# lipo_alarm.net
KiCad netlist of a schematic drawn in Altium Designer
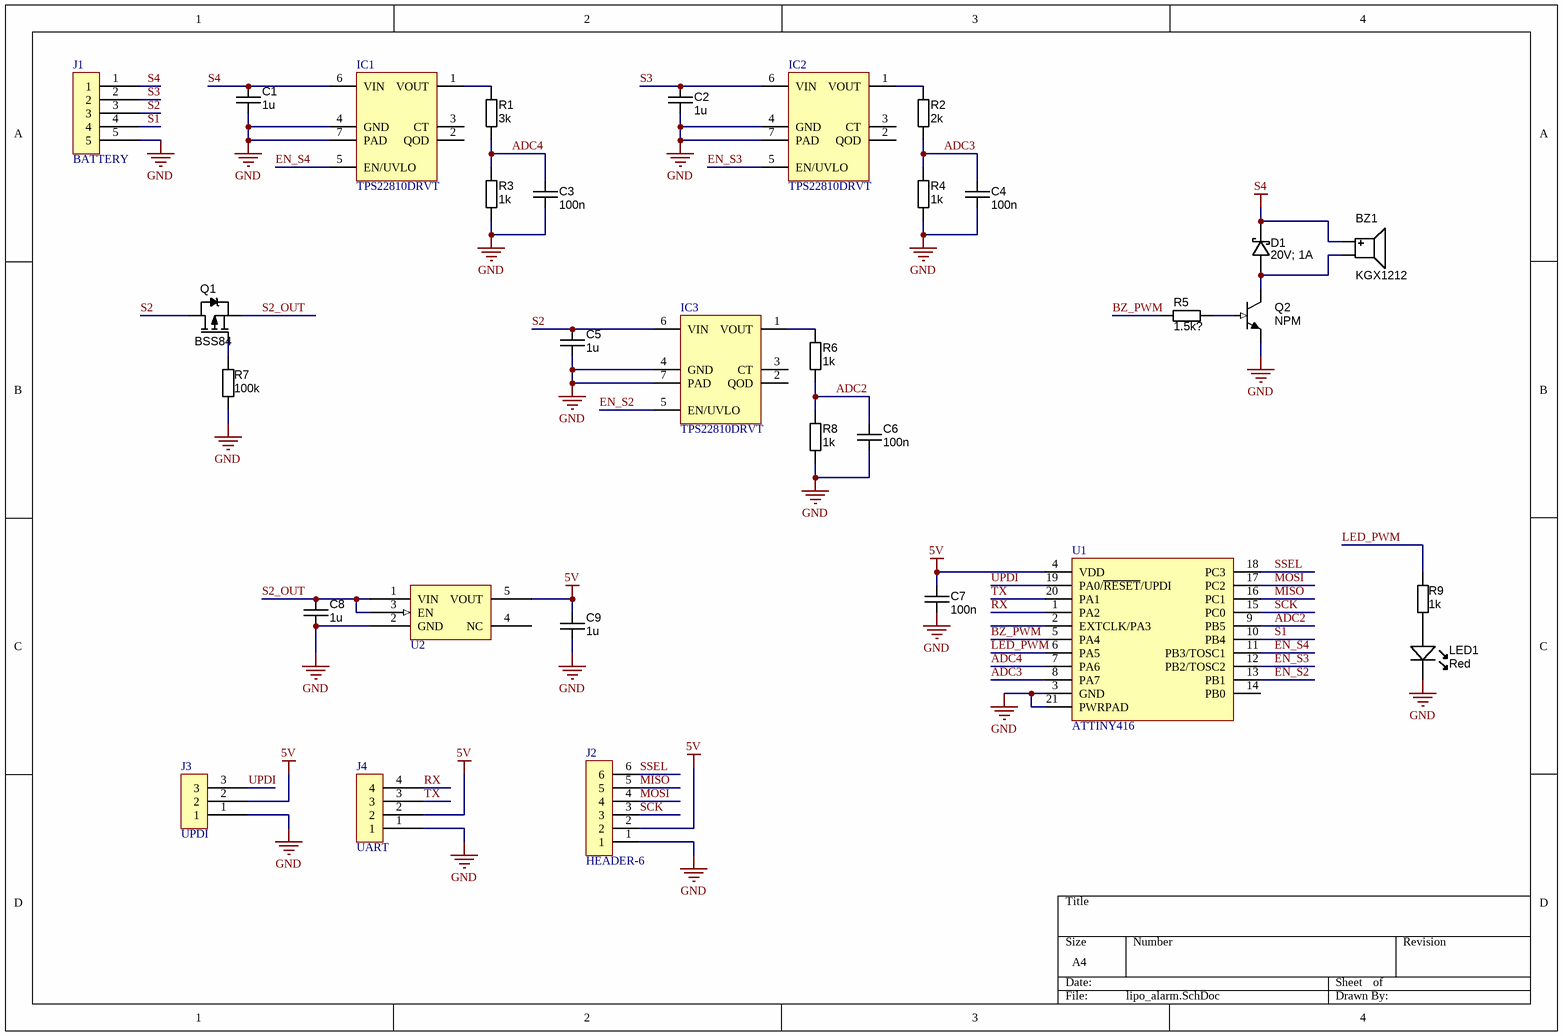
[diagram p0: lipo_alarm.SchDoc]

(export (version "E")
  (design (tool "Eeschema 10.0.6"))
  (components
    (comp (ref "BZ1") (value "KGX1212") (footprint "KXG1212") (libsource (lib "misc") (part "BUZZER")))
    (comp (ref "C1")
      (value "1u")
      (footprint "CAPC1608X90N")
      (description "Capacitor SMD Cer 1uF 10% 16V X7R 0603")
      (fields (field (name "TOLERANCE") "±10%"))
      (libsource (lib "PBL - Capacitors") (part "CAPC_1u_0603_X7R_16V_10%"))
    )
    (comp (ref "C2")
      (value "1u")
      (footprint "CAPC1608X90N")
      (description "Capacitor SMD Cer 1uF 10% 50V X7R 0603")
      (fields (field (name "TOLERANCE") "±10%"))
      (libsource (lib "PBL - Capacitors") (part "CAPC_100n_0603_X7R_50V_10%"))
    )
    (comp (ref "C3")
      (value "100n")
      (footprint "CAPC1608X90N")
      (description "Capacitor SMD Cer 100nF 10% 50V X7R 0603")
      (fields (field (name "TOLERANCE") "±10%"))
      (libsource (lib "PBL - Capacitors") (part "CAPC_100n_0603_X7R_50V_10%"))
    )
    (comp (ref "C4")
      (value "100n")
      (footprint "CAPC1608X90N")
      (description "Capacitor SMD Cer 100nF 10% 50V X7R 0603")
      (fields (field (name "TOLERANCE") "±10%"))
      (libsource (lib "PBL - Capacitors") (part "CAPC_100n_0603_X7R_50V_10%"))
    )
    (comp (ref "C5")
      (value "1u")
      (footprint "CAPC1608X90N")
      (description "Capacitor SMD Cer 1uF 10% 16V X7R 0603")
      (fields (field (name "TOLERANCE") "±10%"))
      (libsource (lib "PBL - Capacitors") (part "CAPC_1u_0603_X7R_16V_10%"))
    )
    (comp (ref "C6")
      (value "100n")
      (footprint "CAPC1608X90N")
      (description "Capacitor SMD Cer 100nF 10% 50V X7R 0603")
      (fields (field (name "TOLERANCE") "±10%"))
      (libsource (lib "PBL - Capacitors") (part "CAPC_100n_0603_X7R_50V_10%"))
    )
    (comp (ref "C7")
      (value "100n")
      (footprint "CAPC1608X90N")
      (description "Capacitor SMD Cer 100nF 10% 50V X7R 0603")
      (fields (field (name "TOLERANCE") "±10%"))
      (libsource (lib "PBL - Capacitors") (part "CAPC_100n_0603_X7R_50V_10%"))
    )
    (comp (ref "C8")
      (value "1u")
      (footprint "CAPC1608X90N")
      (description "Capacitor SMD Cer 2.2uF 10% 10V X5R 0603")
      (fields (field (name "TOLERANCE") "±10%"))
      (libsource (lib "PBL - Capacitors") (part "CAPC_2u2_0603_10V_10%"))
    )
    (comp (ref "C9")
      (value "1u")
      (footprint "CAPC1608X90N")
      (description "Capacitor SMD Cer 2.2uF 10% 10V X5R 0603")
      (fields (field (name "TOLERANCE") "±10%"))
      (libsource (lib "PBL - Capacitors") (part "CAPC_2u2_0603_10V_10%"))
    )
    (comp (ref "D1")
      (value "20V; 1A")
      (footprint "SOD123")
      (description "Diode Schottky SMD 20V 1A SOD123")
      (libsource (lib "PBL - Diodes") (part "DIODE_SCHOTTKY_40V_1A"))
    )
    (comp (ref "IC1")
      (value "TPS22810DRVT")
      (footprint "WSON-6")
      (description "Power Load Switch, 18Vin, 3A, 0.079R, WSON-6, High Side,  TPS22810, TEXAS INSTRUMENTS")
      (fields (field (name "MANUFACTURER") "Texas Instruments"))
      (libsource (lib "power") (part "TPS22810DRVT"))
    )
    (comp (ref "IC2")
      (value "TPS22810DRVT")
      (footprint "WSON-6")
      (description "Power Load Switch, 18Vin, 3A, 0.079R, WSON-6, High Side,  TPS22810, TEXAS INSTRUMENTS")
      (fields (field (name "MANUFACTURER") "Texas Instruments"))
      (libsource (lib "power") (part "TPS22810DRVT"))
    )
    (comp (ref "IC3")
      (value "TPS22810DRVT")
      (footprint "WSON-6")
      (description "Power Load Switch, 18Vin, 3A, 0.079R, WSON-6, High Side,  TPS22810, TEXAS INSTRUMENTS")
      (fields (field (name "MANUFACTURER") "Texas Instruments"))
      (libsource (lib "power") (part "TPS22810DRVT"))
    )
    (comp (ref "J1")
      (value "BATTERY")
      (footprint "JST-XH-5-TH-PCB-CUTOUT")
      (libsource (lib "connectors") (part "HEADER-5"))
    )
    (comp (ref "J2")
      (value "HEADER-6")
      (footprint "MICRO-MATCH-FOB-06")
      (libsource (lib "connectors_micromatch") (part "HEADER-6"))
    )
    (comp (ref "J3")
      (value "UPDI")
      (footprint "PADS-3-1020")
      (libsource (lib "connectors") (part "HEADER-3"))
    )
    (comp (ref "J4")
      (value "UART")
      (footprint "PADS-4-1020")
      (libsource (lib "connectors") (part "HEADER-4"))
    )
    (comp (ref "LED1")
      (value "Red")
      (footprint "LED-0805S-SIDELED-2.1X0.6X1.0")
      (description "LED SMD SIDELED Red 630nm 250mcd 0805")
      (fields (field (name "COLOR") "Red"))
      (libsource (lib "PBL - Light Sources") (part "LED_SMD_RED_0805RA_250mcd"))
    )
    (comp (ref "Q1")
      (value "BSS84")
      (footprint "SOT23-3")
      (description "MOSFET SMD P-CH 50V 130mA SOT23-3")
      (libsource (lib "PBL - Transistors") (part "MOSFET_BSS84"))
    )
    (comp (ref "Q2")
      (value "NPM")
      (footprint "SOT23-3")
      (description "Transistor SMD NPN 15V 3A SOT-23")
      (libsource (lib "PBL - Transistors") (part "NPN_FMMT617TA"))
    )
    (comp (ref "R1")
      (value "3k")
      (footprint "RESC1608X55N")
      (description "Resistor SMD chip 1k Ohm 0.1W 5% 0603")
      (fields (field (name "TOLERANCE") "±5%"))
      (libsource (lib "PBL - Resistors") (part "RES_1K_0603_5%"))
    )
    (comp (ref "R2")
      (value "2k")
      (footprint "RESC1608X55N")
      (description "Resistor SMD chip 1k Ohm 0.1W 5% 0603")
      (fields (field (name "TOLERANCE") "±5%"))
      (libsource (lib "PBL - Resistors") (part "RES_1K_0603_5%"))
    )
    (comp (ref "R3")
      (value "1k")
      (footprint "RESC1608X55N")
      (description "Resistor SMD chip 1k Ohm 0.1W 5% 0603")
      (fields (field (name "TOLERANCE") "±5%"))
      (libsource (lib "PBL - Resistors") (part "RES_1K_0603_5%"))
    )
    (comp (ref "R4")
      (value "1k")
      (footprint "RESC1608X55N")
      (description "Resistor SMD chip 1k Ohm 0.1W 5% 0603")
      (fields (field (name "TOLERANCE") "±5%"))
      (libsource (lib "PBL - Resistors") (part "RES_1K_0603_5%"))
    )
    (comp (ref "R5")
      (value "1.5k?")
      (footprint "RESC1608X55N")
      (description "Resistor SMD chip 1k Ohm 0.1W 5% 0603")
      (fields (field (name "TOLERANCE") "±5%"))
      (libsource (lib "") (part "RES_1K_0603_5%_1"))
    )
    (comp (ref "R6")
      (value "1k")
      (footprint "RESC1608X55N")
      (description "Resistor SMD chip 1k Ohm 0.1W 5% 0603")
      (fields (field (name "TOLERANCE") "±5%"))
      (libsource (lib "PBL - Resistors") (part "RES_1K_0603_5%"))
    )
    (comp (ref "R7")
      (value "100k")
      (footprint "RESC1608X55N")
      (description "Resistor SMD chip 1k Ohm 0.1W 5% 0603")
      (fields (field (name "TOLERANCE") "±5%"))
      (libsource (lib "") (part "RES_1K_0603_5%_1"))
    )
    (comp (ref "R8")
      (value "1k")
      (footprint "RESC1608X55N")
      (description "Resistor SMD chip 1k Ohm 0.1W 5% 0603")
      (fields (field (name "TOLERANCE") "±5%"))
      (libsource (lib "PBL - Resistors") (part "RES_1K_0603_5%"))
    )
    (comp (ref "R9")
      (value "1k")
      (footprint "RESC1608X55N")
      (description "Resistor SMD chip 1k Ohm 0.1W 5% 0603")
      (fields (field (name "TOLERANCE") "±5%"))
      (libsource (lib "PBL - Resistors") (part "RES_1K_0603_5%"))
    )
    (comp (ref "U1")
      (value "ATTINY416")
      (footprint "QFN40P300X300X90_HS-21M")
      (libsource (lib "atmel") (part "ATTINY416"))
    )
    (comp (ref "U2")
      (value "LDO-SOT23-5")
      (footprint "SOT23-5")
      (libsource (lib "power") (part "LDO-SOT23-5"))
    )
  )
  (nets
    (net (code "1") (name "/ADC2") (class "Default")
      (node (ref "C6") (pin "1") (pintype "passive"))
      (node (ref "R6") (pin "2") (pinfunction "2_2") (pintype "passive"))
      (node (ref "R8") (pin "1") (pinfunction "1_1") (pintype "passive"))
      (node (ref "U1") (pin "9") (pinfunction "PB5_9") (pintype "passive"))
    )
    (net (code "2") (name "/ADC3") (class "Default")
      (node (ref "C4") (pin "1") (pintype "passive"))
      (node (ref "R2") (pin "2") (pinfunction "2_2") (pintype "passive"))
      (node (ref "R4") (pin "1") (pinfunction "1_1") (pintype "passive"))
      (node (ref "U1") (pin "8") (pinfunction "PA7_8") (pintype "passive"))
    )
    (net (code "3") (name "/ADC4") (class "Default")
      (node (ref "C3") (pin "1") (pintype "passive"))
      (node (ref "R1") (pin "2") (pinfunction "2_2") (pintype "passive"))
      (node (ref "R3") (pin "1") (pinfunction "1_1") (pintype "passive"))
      (node (ref "U1") (pin "7") (pinfunction "PA6_7") (pintype "passive"))
    )
    (net (code "4") (name "/BZ_PWM") (class "Default")
      (node (ref "R5") (pin "1") (pinfunction "1_1") (pintype "passive"))
      (node (ref "U1") (pin "5") (pinfunction "PA4_5") (pintype "passive"))
    )
    (net (code "5") (name "/EN_S2") (class "Default")
      (node (ref "IC3") (pin "5") (pinfunction "EN/UVLO_5") (pintype "passive"))
      (node (ref "U1") (pin "13") (pinfunction "PB1_13") (pintype "passive"))
    )
    (net (code "6") (name "/EN_S3") (class "Default")
      (node (ref "IC2") (pin "5") (pinfunction "EN/UVLO_5") (pintype "passive"))
      (node (ref "U1") (pin "12") (pinfunction "PB2/TOSC2_12") (pintype "passive"))
    )
    (net (code "7") (name "/EN_S4") (class "Default")
      (node (ref "IC1") (pin "5") (pinfunction "EN/UVLO_5") (pintype "passive"))
      (node (ref "U1") (pin "11") (pinfunction "PB3/TOSC1_11") (pintype "passive"))
    )
    (net (code "8") (name "/LED_PWM") (class "Default")
      (node (ref "R9") (pin "1") (pinfunction "1_1") (pintype "passive"))
      (node (ref "U1") (pin "6") (pinfunction "PA5_6") (pintype "passive"))
    )
    (net (code "9") (name "/MISO") (class "Default")
      (node (ref "J2") (pin "5") (pinfunction "5_5") (pintype "passive"))
      (node (ref "U1") (pin "16") (pinfunction "PC1_16") (pintype "passive"))
    )
    (net (code "10") (name "/MOSI") (class "Default")
      (node (ref "J2") (pin "4") (pinfunction "4_4") (pintype "passive"))
      (node (ref "U1") (pin "17") (pinfunction "PC2_17") (pintype "passive"))
    )
    (net (code "11") (name "/RX") (class "Default")
      (node (ref "J4") (pin "4") (pinfunction "4_4") (pintype "passive"))
      (node (ref "U1") (pin "1") (pinfunction "PA2_1") (pintype "passive"))
    )
    (net (code "12") (name "/S1") (class "Default")
      (node (ref "J1") (pin "4") (pinfunction "4_4") (pintype "passive"))
      (node (ref "U1") (pin "10") (pinfunction "PB4_10") (pintype "passive"))
    )
    (net (code "13") (name "/S2") (class "Default")
      (node (ref "C5") (pin "1") (pintype "passive"))
      (node (ref "IC3") (pin "6") (pinfunction "VIN_6") (pintype "passive"))
      (node (ref "J1") (pin "3") (pinfunction "3_3") (pintype "passive"))
      (node (ref "Q1") (pin "3") (pinfunction "D_3") (pintype "passive"))
    )
    (net (code "14") (name "/S2_OUT") (class "Default")
      (node (ref "C8") (pin "1") (pintype "passive"))
      (node (ref "Q1") (pin "2") (pinfunction "S_2") (pintype "passive"))
      (node (ref "U2") (pin "1") (pinfunction "VIN_1") (pintype "power_in"))
      (node (ref "U2") (pin "3") (pinfunction "EN_3") (pintype "input"))
    )
    (net (code "15") (name "/S3") (class "Default")
      (node (ref "C2") (pin "1") (pintype "passive"))
      (node (ref "IC2") (pin "6") (pinfunction "VIN_6") (pintype "passive"))
      (node (ref "J1") (pin "2") (pinfunction "2_2") (pintype "passive"))
    )
    (net (code "16") (name "/SCK") (class "Default")
      (node (ref "J2") (pin "3") (pinfunction "3_3") (pintype "passive"))
      (node (ref "U1") (pin "15") (pinfunction "PC0_15") (pintype "passive"))
    )
    (net (code "17") (name "/SSEL") (class "Default")
      (node (ref "J2") (pin "6") (pinfunction "6_6") (pintype "passive"))
      (node (ref "U1") (pin "18") (pinfunction "PC3_18") (pintype "passive"))
    )
    (net (code "18") (name "/TX") (class "Default")
      (node (ref "J4") (pin "3") (pinfunction "3_3") (pintype "passive"))
      (node (ref "U1") (pin "20") (pinfunction "PA1_20") (pintype "passive"))
    )
    (net (code "19") (name "/UPDI") (class "Default")
      (node (ref "J3") (pin "3") (pinfunction "3_3") (pintype "passive"))
      (node (ref "U1") (pin "19") (pinfunction "PA0/~{RESET}/UPDI_19") (pintype "passive"))
    )
    (net (code "20") (name "5V") (class "Default")
      (node (ref "C7") (pin "1") (pintype "passive"))
      (node (ref "C9") (pin "1") (pintype "passive"))
      (node (ref "J2") (pin "2") (pinfunction "2_2") (pintype "passive"))
      (node (ref "J3") (pin "2") (pinfunction "2_2") (pintype "passive"))
      (node (ref "J4") (pin "2") (pinfunction "2_2") (pintype "passive"))
      (node (ref "U1") (pin "4") (pinfunction "VDD_4") (pintype "passive"))
      (node (ref "U2") (pin "5") (pinfunction "VOUT_5") (pintype "passive"))
    )
    (net (code "21") (name "GND") (class "Default")
      (node (ref "C1") (pin "2") (pintype "passive"))
      (node (ref "C2") (pin "2") (pintype "passive"))
      (node (ref "C3") (pin "2") (pintype "passive"))
      (node (ref "C4") (pin "2") (pintype "passive"))
      (node (ref "C5") (pin "2") (pintype "passive"))
      (node (ref "C6") (pin "2") (pintype "passive"))
      (node (ref "C7") (pin "2") (pintype "passive"))
      (node (ref "C8") (pin "2") (pintype "passive"))
      (node (ref "C9") (pin "2") (pintype "passive"))
      (node (ref "IC1") (pin "4") (pinfunction "GND_4") (pintype "passive"))
      (node (ref "IC1") (pin "7") (pinfunction "PAD_7") (pintype "passive"))
      (node (ref "IC2") (pin "4") (pinfunction "GND_4") (pintype "passive"))
      (node (ref "IC2") (pin "7") (pinfunction "PAD_7") (pintype "passive"))
      (node (ref "IC3") (pin "4") (pinfunction "GND_4") (pintype "passive"))
      (node (ref "IC3") (pin "7") (pinfunction "PAD_7") (pintype "passive"))
      (node (ref "J1") (pin "5") (pinfunction "5_5") (pintype "passive"))
      (node (ref "J2") (pin "1") (pinfunction "1_1") (pintype "passive"))
      (node (ref "J3") (pin "1") (pinfunction "1_1") (pintype "passive"))
      (node (ref "J4") (pin "1") (pinfunction "1_1") (pintype "passive"))
      (node (ref "LED1") (pin "K") (pinfunction "K_K") (pintype "passive"))
      (node (ref "Q2") (pin "2") (pinfunction "E_2") (pintype "passive"))
      (node (ref "R3") (pin "2") (pinfunction "2_2") (pintype "passive"))
      (node (ref "R4") (pin "2") (pinfunction "2_2") (pintype "passive"))
      (node (ref "R7") (pin "1") (pinfunction "1_1") (pintype "passive"))
      (node (ref "R8") (pin "2") (pinfunction "2_2") (pintype "passive"))
      (node (ref "U1") (pin "21") (pinfunction "PWRPAD_21") (pintype "passive"))
      (node (ref "U1") (pin "3") (pinfunction "GND_3") (pintype "passive"))
      (node (ref "U2") (pin "2") (pinfunction "GND_2") (pintype "power_in"))
    )
    (net (code "22") (name "Net-(BZ1-Negative)") (class "Default")
      (node (ref "BZ1") (pin "2") (pinfunction "Negative_2") (pintype "passive"))
      (node (ref "D1") (pin "A") (pinfunction "A_A") (pintype "passive"))
      (node (ref "Q2") (pin "3") (pinfunction "C_3") (pintype "passive"))
    )
    (net (code "23") (name "Net-(IC1-VOUT)") (class "Default")
      (node (ref "IC1") (pin "1") (pinfunction "VOUT_1") (pintype "passive"))
      (node (ref "R1") (pin "1") (pinfunction "1_1") (pintype "passive"))
    )
    (net (code "24") (name "Net-(IC2-VOUT)") (class "Default")
      (node (ref "IC2") (pin "1") (pinfunction "VOUT_1") (pintype "passive"))
      (node (ref "R2") (pin "1") (pinfunction "1_1") (pintype "passive"))
    )
    (net (code "25") (name "Net-(IC3-VOUT)") (class "Default")
      (node (ref "IC3") (pin "1") (pinfunction "VOUT_1") (pintype "passive"))
      (node (ref "R6") (pin "1") (pinfunction "1_1") (pintype "passive"))
    )
    (net (code "26") (name "Net-(LED1-PadA)") (class "Default")
      (node (ref "LED1") (pin "A") (pinfunction "A_A") (pintype "passive"))
      (node (ref "R9") (pin "2") (pinfunction "2_2") (pintype "passive"))
    )
    (net (code "27") (name "Net-(Q1-G)") (class "Default")
      (node (ref "Q1") (pin "1") (pinfunction "G_1") (pintype "passive"))
      (node (ref "R7") (pin "2") (pinfunction "2_2") (pintype "passive"))
    )
    (net (code "28") (name "Net-(Q2-B)") (class "Default")
      (node (ref "Q2") (pin "1") (pinfunction "B_1") (pintype "input"))
      (node (ref "R5") (pin "2") (pinfunction "2_2") (pintype "passive"))
    )
    (net (code "29") (name "S4") (class "Default")
      (node (ref "BZ1") (pin "1") (pinfunction "Positive_1") (pintype "passive"))
      (node (ref "C1") (pin "1") (pintype "passive"))
      (node (ref "D1") (pin "K") (pinfunction "K_K") (pintype "passive"))
      (node (ref "IC1") (pin "6") (pinfunction "VIN_6") (pintype "passive"))
      (node (ref "J1") (pin "1") (pinfunction "1_1") (pintype "passive"))
    )
    (net (code "30") (name "unconnected-(IC1-CT-Pad3)") (class "Default")
      (node (ref "IC1") (pin "3") (pinfunction "CT_3") (pintype "passive"))
    )
    (net (code "31") (name "unconnected-(IC1-QOD-Pad2)") (class "Default")
      (node (ref "IC1") (pin "2") (pinfunction "QOD_2") (pintype "passive"))
    )
    (net (code "32") (name "unconnected-(IC2-CT-Pad3)") (class "Default")
      (node (ref "IC2") (pin "3") (pinfunction "CT_3") (pintype "passive"))
    )
    (net (code "33") (name "unconnected-(IC2-QOD-Pad2)") (class "Default")
      (node (ref "IC2") (pin "2") (pinfunction "QOD_2") (pintype "passive"))
    )
    (net (code "34") (name "unconnected-(IC3-CT-Pad3)") (class "Default")
      (node (ref "IC3") (pin "3") (pinfunction "CT_3") (pintype "passive"))
    )
    (net (code "35") (name "unconnected-(IC3-QOD-Pad2)") (class "Default")
      (node (ref "IC3") (pin "2") (pinfunction "QOD_2") (pintype "passive"))
    )
    (net (code "36") (name "unconnected-(U1-EXTCLK{slash}PA3-Pad2)") (class "Default")
      (node (ref "U1") (pin "2") (pinfunction "EXTCLK/PA3_2") (pintype "passive"))
    )
    (net (code "37") (name "unconnected-(U1-PB0-Pad14)") (class "Default")
      (node (ref "U1") (pin "14") (pinfunction "PB0_14") (pintype "passive"))
    )
    (net (code "38") (name "unconnected-(U2-NC-Pad4)") (class "Default")
      (node (ref "U2") (pin "4") (pinfunction "NC_4") (pintype "power_in"))
    )
  )
)
